# Measurement.net
KiCad netlist of a schematic drawn in Altium Designer
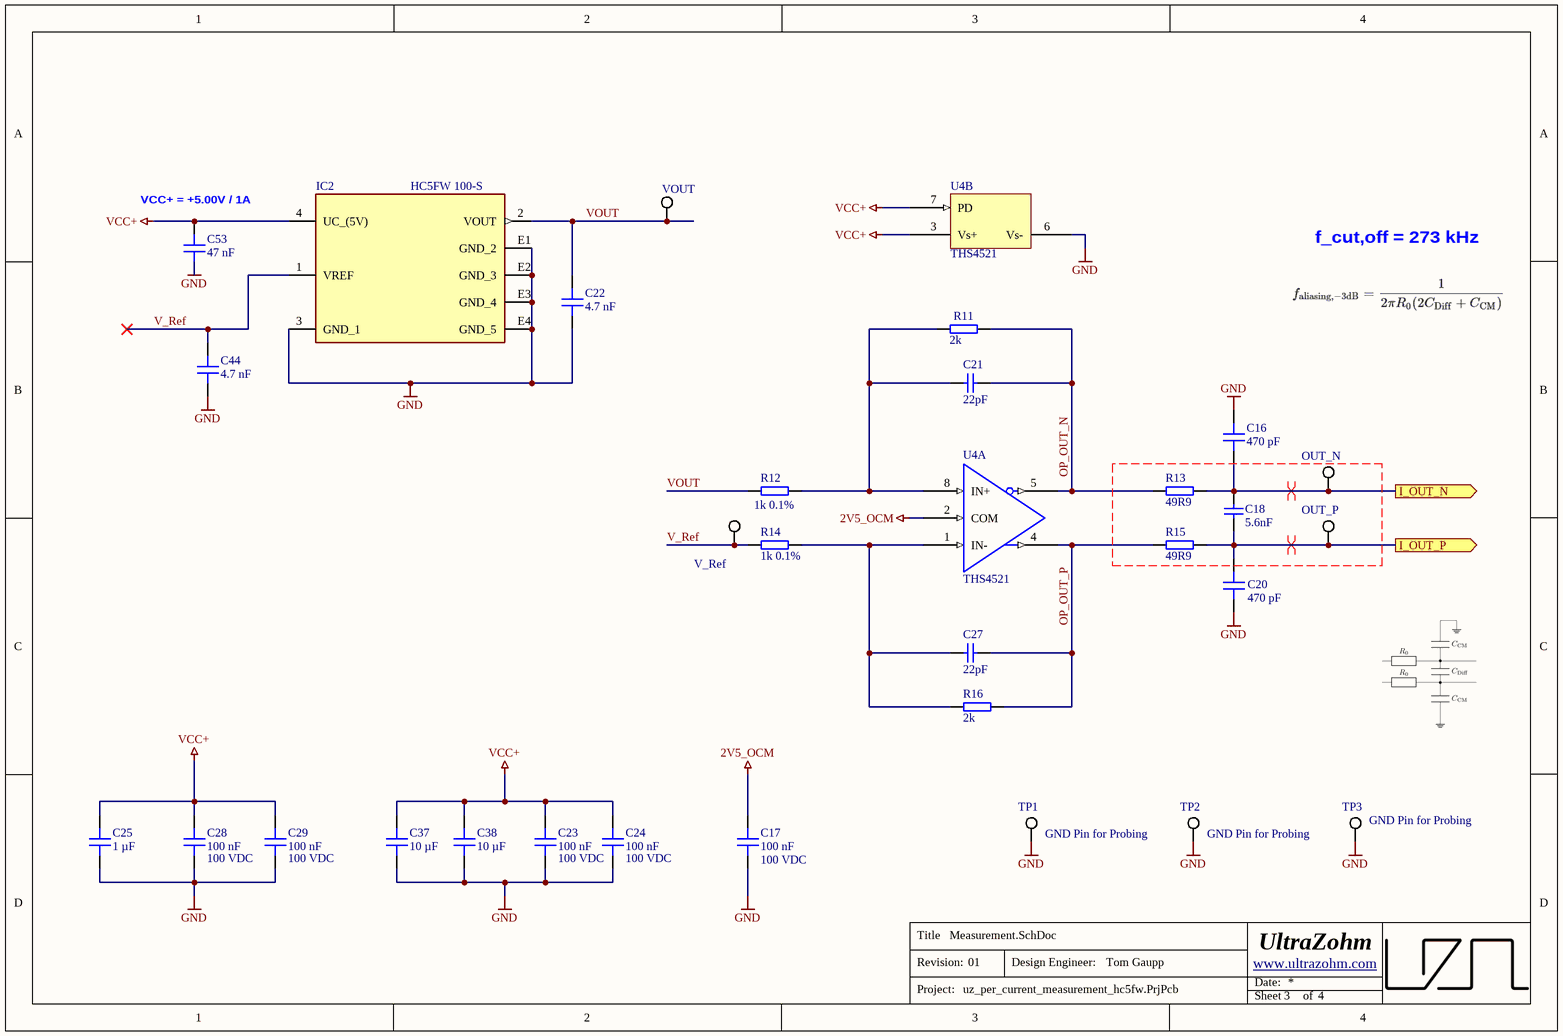
[diagram p0: Measurement.SchDoc]

(export (version "E")
  (design (tool "Eeschema 10.0.6"))
  (components
    (comp (ref "C16")
      (value "470 pF")
      (footprint "C_0603")
      (description "50V 470pF X7R ±10% 0603 Multilayer Ceramic Capacitors MLCC - SMD/SMT ROHS")
      (fields
        (field (name "MANUFACTURER PART NUMBER") "C0603C471K5RACAUTO")
        (field (name "MANUFACTURER") "KEMET")
        (field (name "CREATED FROM") "KIlhan")
      )
      (libsource (lib "user") (part "Capacitor"))
    )
    (comp (ref "C17")
      (value "100 nF")
      (footprint "C_0603")
      (description "100V 100nF X7S ±10% 0603 Multilayer Ceramic Capacitors MLCC - SMD/SMT ROHS")
      (fields
        (field (name "MANUFACTURER PART NUMBER") "C1608X7S2A104KT000N")
        (field (name "MANUFACTURER") "TDK")
        (field (name "VOLTAGE RATING") "100 VDC")
        (field (name "CREATED FROM") "AGeiger")
      )
      (libsource (lib "user") (part "Capacitor"))
    )
    (comp (ref "C18")
      (value "5.6nF")
      (footprint "C_0603_TE")
      (description "50V 5.6nF X7R ±10% 0603 Multilayer Ceramic Capacitors MLCC - SMD/SMT ROHS")
      (fields
        (field (name "MANUFACTURER PART NUMBER") "0603B562K500NT")
        (field (name "MANUFACTURER") "FH (Guangdong Fenghua Advanced Tech)")
        (field (name "CREATED FROM") "Kilhan")
      )
      (libsource (lib "user") (part "CAP-NP"))
    )
    (comp (ref "C20")
      (value "470 pF")
      (footprint "C_0603")
      (description "50V 470pF X7R ±10% 0603 Multilayer Ceramic Capacitors MLCC - SMD/SMT ROHS")
      (fields
        (field (name "MANUFACTURER PART NUMBER") "C0603C471K5RACAUTO")
        (field (name "MANUFACTURER") "KEMET")
        (field (name "CREATED FROM") "KIlhan")
      )
      (libsource (lib "user") (part "Capacitor"))
    )
    (comp (ref "C21")
      (value "22pF")
      (footprint "C_0603_TE")
      (description "50V 22pF C0G ±5% 0603 Multilayer Ceramic Capacitors MLCC - SMD/SMT ROHS")
      (fields
        (field (name "MANUFACTURER PART NUMBER") "CL10C220JB8NNNC")
        (field (name "MANUFACTURER") "Samsung Electro-Mechanics")
        (field (name "CREATED FROM") "Kilhan")
      )
      (libsource (lib "user") (part "CAP-NP"))
    )
    (comp (ref "C22")
      (value "4.7 nF")
      (footprint "C_0603")
      (description "Capacitor 0603, 16 VDC, 4.7 nF, X7R")
      (fields
        (field (name "MANUFACTURER PART NUMBER") "C0603C472K4RECAUTO")
        (field (name "MANUFACTURER") "KEMET")
        (field (name "CREATED FROM") "MGremer")
      )
      (libsource (lib "user") (part "Capacitor"))
    )
    (comp (ref "C23")
      (value "100 nF")
      (footprint "C_0603")
      (description "100V 100nF X7S ±10% 0603 Multilayer Ceramic Capacitors MLCC - SMD/SMT ROHS")
      (fields
        (field (name "MANUFACTURER PART NUMBER") "C1608X7S2A104KT000N")
        (field (name "MANUFACTURER") "TDK")
        (field (name "VOLTAGE RATING") "100 VDC")
        (field (name "CREATED FROM") "AGeiger")
      )
      (libsource (lib "user") (part "Capacitor"))
    )
    (comp (ref "C24")
      (value "100 nF")
      (footprint "C_0603")
      (description "100V 100nF X7S ±10% 0603 Multilayer Ceramic Capacitors MLCC - SMD/SMT ROHS")
      (fields
        (field (name "MANUFACTURER PART NUMBER") "C1608X7S2A104KT000N")
        (field (name "MANUFACTURER") "TDK")
        (field (name "VOLTAGE RATING") "100 VDC")
        (field (name "CREATED FROM") "AGeiger")
      )
      (libsource (lib "user") (part "Capacitor"))
    )
    (comp (ref "C25")
      (value "1 µF")
      (footprint "C_0603")
      (description "50V 1uF X5R ±10% 0603  Multilayer Ceramic Capacitors MLCC - SMD/SMT ROHS")
      (fields
        (field (name "MANUFACTURER PART NUMBER") "CL10A105KB8NNNC")
        (field (name "MANUFACTURER") "Samsung Electro-Mechanics")
        (field (name "CREATED FROM") "MGremer")
      )
      (libsource (lib "user") (part "Capacitor"))
    )
    (comp (ref "C27")
      (value "22pF")
      (footprint "C_0603_TE")
      (description "50V 22pF C0G ±5% 0603 Multilayer Ceramic Capacitors MLCC - SMD/SMT ROHS")
      (fields
        (field (name "MANUFACTURER PART NUMBER") "CL10C220JB8NNNC")
        (field (name "MANUFACTURER") "Samsung Electro-Mechanics")
        (field (name "CREATED FROM") "Kilhan")
      )
      (libsource (lib "user") (part "CAP-NP"))
    )
    (comp (ref "C28")
      (value "100 nF")
      (footprint "C_0603")
      (description "100V 100nF X7S ±10% 0603 Multilayer Ceramic Capacitors MLCC - SMD/SMT ROHS")
      (fields
        (field (name "MANUFACTURER PART NUMBER") "C1608X7S2A104KT000N")
        (field (name "MANUFACTURER") "TDK")
        (field (name "VOLTAGE RATING") "100 VDC")
        (field (name "CREATED FROM") "AGeiger")
      )
      (libsource (lib "user") (part "Capacitor"))
    )
    (comp (ref "C29")
      (value "100 nF")
      (footprint "C_0603")
      (description "100V 100nF X7S ±10% 0603 Multilayer Ceramic Capacitors MLCC - SMD/SMT ROHS")
      (fields
        (field (name "MANUFACTURER PART NUMBER") "C1608X7S2A104KT000N")
        (field (name "MANUFACTURER") "TDK")
        (field (name "VOLTAGE RATING") "100 VDC")
        (field (name "CREATED FROM") "AGeiger")
      )
      (libsource (lib "user") (part "Capacitor"))
    )
    (comp (ref "C37")
      (value "10 µF")
      (footprint "C0805")
      (description "Capacitor 0805, 35 VDC, 10 µF, X5R")
      (fields
        (field (name "MANUFACTURER PART NUMBER") "GRM21BR6YA106KE43L")
        (field (name "MANUFACTURER") "muRata")
        (field (name "CREATED FROM") "MGremer")
      )
      (libsource (lib "user") (part "Capacitor"))
    )
    (comp (ref "C38")
      (value "10 µF")
      (footprint "C0805")
      (description "Capacitor 0805, 35 VDC, 10 µF, X5R")
      (fields
        (field (name "MANUFACTURER PART NUMBER") "GRM21BR6YA106KE43L")
        (field (name "MANUFACTURER") "muRata")
        (field (name "CREATED FROM") "MGremer")
      )
      (libsource (lib "user") (part "Capacitor"))
    )
    (comp (ref "C44")
      (value "4.7 nF")
      (footprint "C_0603")
      (description "Capacitor 0603, 16 VDC, 4.7 nF, X7R")
      (fields
        (field (name "MANUFACTURER PART NUMBER") "C0603C472K4RECAUTO")
        (field (name "MANUFACTURER") "KEMET")
        (field (name "CREATED FROM") "MGremer")
      )
      (libsource (lib "user") (part "Capacitor"))
    )
    (comp (ref "C53")
      (value "47 nF")
      (footprint "C_0603")
      (description "Capacitor 0603, 50 VDC, 47 nF, X7R")
      (fields
        (field (name "MANUFACTURER PART NUMBER") "CL10B473KB8NNNC")
        (field (name "MANUFACTURER") "Samsung Electro-Mechanics")
        (field (name "CREATED FROM") "DHufnagel")
      )
      (libsource (lib "user") (part "Capacitor"))
    )
    (comp (ref "IC2")
      (value "HC5FW 100-S")
      (footprint "LEM_HC5FW")
      (description "-100 A - 100 A, 40 kHz")
      (fields (field (name "MANUFACTURER") "LEM") (field (name "CREATED FROM") "TGaupp"))
      (libsource (lib "user") (part "LEM_HC5FW"))
    )
    (comp (ref "OUT_N")
      (value "5015")
      (footprint "KSTN-5019_V")
      (description "Circuit Board Hardware - PCB SM TEST POINT ON T&R - MINIATURE")
      (fields
        (field (name "MANUFACTURER") "Keystone Electronics")
        (field (name "LCSC PART NUMBER") "C5199798")
        (field (name "CREATED FROM") "AGeiger")
      )
      (libsource (lib "user") (part "SMD Testpoint"))
    )
    (comp (ref "OUT_P")
      (value "5015")
      (footprint "KSTN-5019_V")
      (description "Circuit Board Hardware - PCB SM TEST POINT ON T&R - MINIATURE")
      (fields
        (field (name "MANUFACTURER") "Keystone Electronics")
        (field (name "LCSC PART NUMBER") "C5199798")
        (field (name "CREATED FROM") "AGeiger")
      )
      (libsource (lib "user") (part "SMD Testpoint"))
    )
    (comp (ref "R11")
      (value "2k")
      (footprint "RES 0603_1608")
      (description "SMD resistor 0.1%")
      (fields
        (field (name "MANUFACTURER PART NUMBER") "ERJ-PB3B2001V")
        (field (name "MANUFACTURER") "Panasonic")
        (field (name "CREATED FROM") "DHufnagel")
      )
      (libsource (lib "user") (part "Resistor"))
    )
    (comp (ref "R12")
      (value "1k 0.1%")
      (footprint "RES 0603_1608")
      (description "100mW ±0.1% ±25ppm/℃ 1kΩ 0603 Chip Resistor - Surface Mount ROHS")
      (fields
        (field (name "MANUFACTURER PART NUMBER") "AR03BTCX1001")
        (field (name "MANUFACTURER") "Viking Tech")
        (field (name "CREATED FROM") "AGeiger")
      )
      (libsource (lib "user") (part "Resistor"))
    )
    (comp (ref "R13")
      (value "49R9")
      (footprint "RES 0603_1608")
      (description "100mW Thick Film Resistors ±100ppm/℃ ±1% 49.9Ω 0603 Chip Resistor - Surface Mount ROHS")
      (fields
        (field (name "MANUFACTURER PART NUMBER") "RC0603FR-0749R9L")
        (field (name "MANUFACTURER") "YAGEO")
        (field (name "CREATED FROM") "AGeiger")
      )
      (libsource (lib "user") (part "Resistor"))
    )
    (comp (ref "R14")
      (value "1k 0.1%")
      (footprint "RES 0603_1608")
      (description "100mW ±0.1% ±25ppm/℃ 1kΩ 0603 Chip Resistor - Surface Mount ROHS")
      (fields
        (field (name "MANUFACTURER PART NUMBER") "AR03BTCX1001")
        (field (name "MANUFACTURER") "Viking Tech")
        (field (name "CREATED FROM") "AGeiger")
      )
      (libsource (lib "user") (part "Resistor"))
    )
    (comp (ref "R15")
      (value "49R9")
      (footprint "RES 0603_1608")
      (description "100mW Thick Film Resistors ±100ppm/℃ ±1% 49.9Ω 0603 Chip Resistor - Surface Mount ROHS")
      (fields
        (field (name "MANUFACTURER PART NUMBER") "RC0603FR-0749R9L")
        (field (name "MANUFACTURER") "YAGEO")
        (field (name "CREATED FROM") "AGeiger")
      )
      (libsource (lib "user") (part "Resistor"))
    )
    (comp (ref "R16")
      (value "2k")
      (footprint "RES 0603_1608")
      (description "SMD resistor 0.1%")
      (fields
        (field (name "MANUFACTURER PART NUMBER") "ERJ-PB3B2001V")
        (field (name "MANUFACTURER") "Panasonic")
        (field (name "CREATED FROM") "DHufnagel")
      )
      (libsource (lib "user") (part "Resistor"))
    )
    (comp (ref "TP1")
      (value "5015")
      (footprint "KSTN-5019_V")
      (description "Circuit Board Hardware - PCB SM TEST POINT ON T&R - MINIATURE")
      (fields
        (field (name "MANUFACTURER") "Keystone Electronics")
        (field (name "LCSC PART NUMBER") "C5199798")
        (field (name "CREATED FROM") "AGeiger")
      )
      (libsource (lib "user") (part "SMD Testpoint"))
    )
    (comp (ref "TP2")
      (value "5015")
      (footprint "KSTN-5019_V")
      (description "Circuit Board Hardware - PCB SM TEST POINT ON T&R - MINIATURE")
      (fields
        (field (name "MANUFACTURER") "Keystone Electronics")
        (field (name "LCSC PART NUMBER") "C5199798")
        (field (name "CREATED FROM") "AGeiger")
      )
      (libsource (lib "user") (part "SMD Testpoint"))
    )
    (comp (ref "TP3")
      (value "5015")
      (footprint "KSTN-5019_V")
      (description "Circuit Board Hardware - PCB SM TEST POINT ON T&R - MINIATURE")
      (fields
        (field (name "MANUFACTURER") "Keystone Electronics")
        (field (name "LCSC PART NUMBER") "C5199798")
        (field (name "CREATED FROM") "AGeiger")
      )
      (libsource (lib "user") (part "SMD Testpoint"))
    )
    (comp (ref "U4")
      (value "THS4521")
      (footprint "SOIC127P600X175-8N")
      (description "THS452x Very Low Power, Negative Rail Input, Rail-To-Rail Output, Fully Differential Amplifier")
      (fields
        (field (name "MANUFACTURER PART NUMBER") "THS4521IDR")
        (field (name "MANUFACTURER") "Texas Instruments")
        (field (name "CREATED FROM") "AGeiger")
      )
      (libsource (lib "user") (part "THS4521"))
    )
    (comp (ref "VOUT")
      (value "5019")
      (footprint "KSTN-5019_V")
      (description "Circuit Board Hardware - PCB SM TEST POINT ON T&R - MINIATURE")
      (fields
        (field (name "MANUFACTURER") "Keystone Electronics")
        (field (name "LCSC PART NUMBER") "C5199800")
        (field (name "CREATED FROM") "AGeiger")
      )
      (libsource (lib "user") (part "SMD Testpoint"))
    )
    (comp (ref "V_Ref")
      (value "5015")
      (footprint "KSTN-5019_V")
      (description "Circuit Board Hardware - PCB SM TEST POINT ON T&R - MINIATURE")
      (fields
        (field (name "MANUFACTURER") "Keystone Electronics")
        (field (name "LCSC PART NUMBER") "C5199798")
        (field (name "CREATED FROM") "AGeiger")
      )
      (libsource (lib "user") (part "SMD Testpoint"))
    )
  )
  (nets
    (net (code "1") (name "/I_OUT_N") (class "Default")
      (node (ref "C16") (pin "2") (pinfunction "2_2") (pintype "passive"))
      (node (ref "C18") (pin "1") (pinfunction "1_1") (pintype "passive"))
      (node (ref "OUT_N") (pin "1") (pinfunction "1_1") (pintype "passive"))
      (node (ref "R13") (pin "2") (pinfunction "2_2") (pintype "passive"))
    )
    (net (code "2") (name "/I_OUT_P") (class "Default")
      (node (ref "C18") (pin "2") (pinfunction "2_2") (pintype "passive"))
      (node (ref "C20") (pin "1") (pinfunction "1_1") (pintype "passive"))
      (node (ref "OUT_P") (pin "1") (pinfunction "1_1") (pintype "passive"))
      (node (ref "R15") (pin "2") (pinfunction "2_2") (pintype "passive"))
    )
    (net (code "3") (name "/OP_OUT_N") (class "Default")
      (node (ref "C21") (pin "1") (pinfunction "1_1") (pintype "passive"))
      (node (ref "R11") (pin "2") (pinfunction "2_2") (pintype "passive"))
      (node (ref "R13") (pin "1") (pinfunction "1_1") (pintype "passive"))
      (node (ref "U4") (pin "5") (pinfunction "OUT-_5") (pintype "output"))
    )
    (net (code "4") (name "/OP_OUT_P") (class "Default")
      (node (ref "C27") (pin "1") (pinfunction "1_1") (pintype "passive"))
      (node (ref "R15") (pin "1") (pinfunction "1_1") (pintype "passive"))
      (node (ref "R16") (pin "2") (pinfunction "2_2") (pintype "passive"))
      (node (ref "U4") (pin "4") (pinfunction "OUT+_4") (pintype "output"))
    )
    (net (code "5") (name "/VOUT") (class "Default")
      (node (ref "C22") (pin "2") (pinfunction "2_2") (pintype "passive"))
      (node (ref "IC2") (pin "2") (pinfunction "VOUT_2") (pintype "output"))
      (node (ref "R12") (pin "1") (pinfunction "1_1") (pintype "passive"))
      (node (ref "VOUT") (pin "1") (pinfunction "1_1") (pintype "passive"))
    )
    (net (code "6") (name "/V_Ref") (class "Default")
      (node (ref "C44") (pin "2") (pinfunction "2_2") (pintype "passive"))
      (node (ref "IC2") (pin "1") (pinfunction "VREF_1") (pintype "passive"))
      (node (ref "R14") (pin "1") (pinfunction "1_1") (pintype "passive"))
      (node (ref "V_Ref") (pin "1") (pinfunction "1_1") (pintype "passive"))
    )
    (net (code "7") (name "2V5_OCM") (class "Default")
      (node (ref "C17") (pin "1") (pinfunction "1_1") (pintype "passive"))
      (node (ref "U4") (pin "2") (pinfunction "COM_2") (pintype "input"))
    )
    (net (code "8") (name "GND") (class "Default")
      (node (ref "C16") (pin "1") (pinfunction "1_1") (pintype "passive"))
      (node (ref "C17") (pin "2") (pinfunction "2_2") (pintype "passive"))
      (node (ref "C20") (pin "2") (pinfunction "2_2") (pintype "passive"))
      (node (ref "C22") (pin "1") (pinfunction "1_1") (pintype "passive"))
      (node (ref "C23") (pin "1") (pinfunction "1_1") (pintype "passive"))
      (node (ref "C24") (pin "1") (pinfunction "1_1") (pintype "passive"))
      (node (ref "C25") (pin "1") (pinfunction "1_1") (pintype "passive"))
      (node (ref "C28") (pin "1") (pinfunction "1_1") (pintype "passive"))
      (node (ref "C29") (pin "1") (pinfunction "1_1") (pintype "passive"))
      (node (ref "C37") (pin "1") (pinfunction "1_1") (pintype "passive"))
      (node (ref "C38") (pin "1") (pinfunction "1_1") (pintype "passive"))
      (node (ref "C44") (pin "1") (pinfunction "1_1") (pintype "passive"))
      (node (ref "C53") (pin "1") (pinfunction "1_1") (pintype "passive"))
      (node (ref "IC2") (pin "3") (pinfunction "GND_1_3") (pintype "passive"))
      (node (ref "IC2") (pin "E1") (pinfunction "GND_2_E1") (pintype "passive"))
      (node (ref "IC2") (pin "E2") (pinfunction "GND_3_E2") (pintype "passive"))
      (node (ref "IC2") (pin "E3") (pinfunction "GND_4_E3") (pintype "passive"))
      (node (ref "IC2") (pin "E4") (pinfunction "GND_5_E4") (pintype "passive"))
      (node (ref "TP1") (pin "1") (pinfunction "1_1") (pintype "passive"))
      (node (ref "TP2") (pin "1") (pinfunction "1_1") (pintype "passive"))
      (node (ref "TP3") (pin "1") (pinfunction "1_1") (pintype "passive"))
      (node (ref "U4") (pin "6") (pinfunction "Vs-_6") (pintype "power_in"))
    )
    (net (code "9") (name "Net-(U4A-IN+)") (class "Default")
      (node (ref "C21") (pin "2") (pinfunction "2_2") (pintype "passive"))
      (node (ref "R11") (pin "1") (pinfunction "1_1") (pintype "passive"))
      (node (ref "R12") (pin "2") (pinfunction "2_2") (pintype "passive"))
      (node (ref "U4") (pin "8") (pinfunction "IN+_8") (pintype "input"))
    )
    (net (code "10") (name "Net-(U4A-IN-)") (class "Default")
      (node (ref "C27") (pin "2") (pinfunction "2_2") (pintype "passive"))
      (node (ref "R14") (pin "2") (pinfunction "2_2") (pintype "passive"))
      (node (ref "R16") (pin "1") (pinfunction "1_1") (pintype "passive"))
      (node (ref "U4") (pin "1") (pinfunction "IN-_1") (pintype "input"))
    )
    (net (code "11") (name "VCC+") (class "Default")
      (node (ref "C23") (pin "2") (pinfunction "2_2") (pintype "passive"))
      (node (ref "C24") (pin "2") (pinfunction "2_2") (pintype "passive"))
      (node (ref "C25") (pin "2") (pinfunction "2_2") (pintype "passive"))
      (node (ref "C28") (pin "2") (pinfunction "2_2") (pintype "passive"))
      (node (ref "C29") (pin "2") (pinfunction "2_2") (pintype "passive"))
      (node (ref "C37") (pin "2") (pinfunction "2_2") (pintype "passive"))
      (node (ref "C38") (pin "2") (pinfunction "2_2") (pintype "passive"))
      (node (ref "C53") (pin "2") (pinfunction "2_2") (pintype "passive"))
      (node (ref "IC2") (pin "4") (pinfunction "UC_(5V)_4") (pintype "passive"))
      (node (ref "U4") (pin "3") (pinfunction "Vs+_3") (pintype "power_in"))
      (node (ref "U4") (pin "7") (pinfunction "PD_7") (pintype "input"))
    )
  )
)
